# Arduino_PowerMeter_Shield.net
KiCad netlist of a schematic drawn in EAGLE
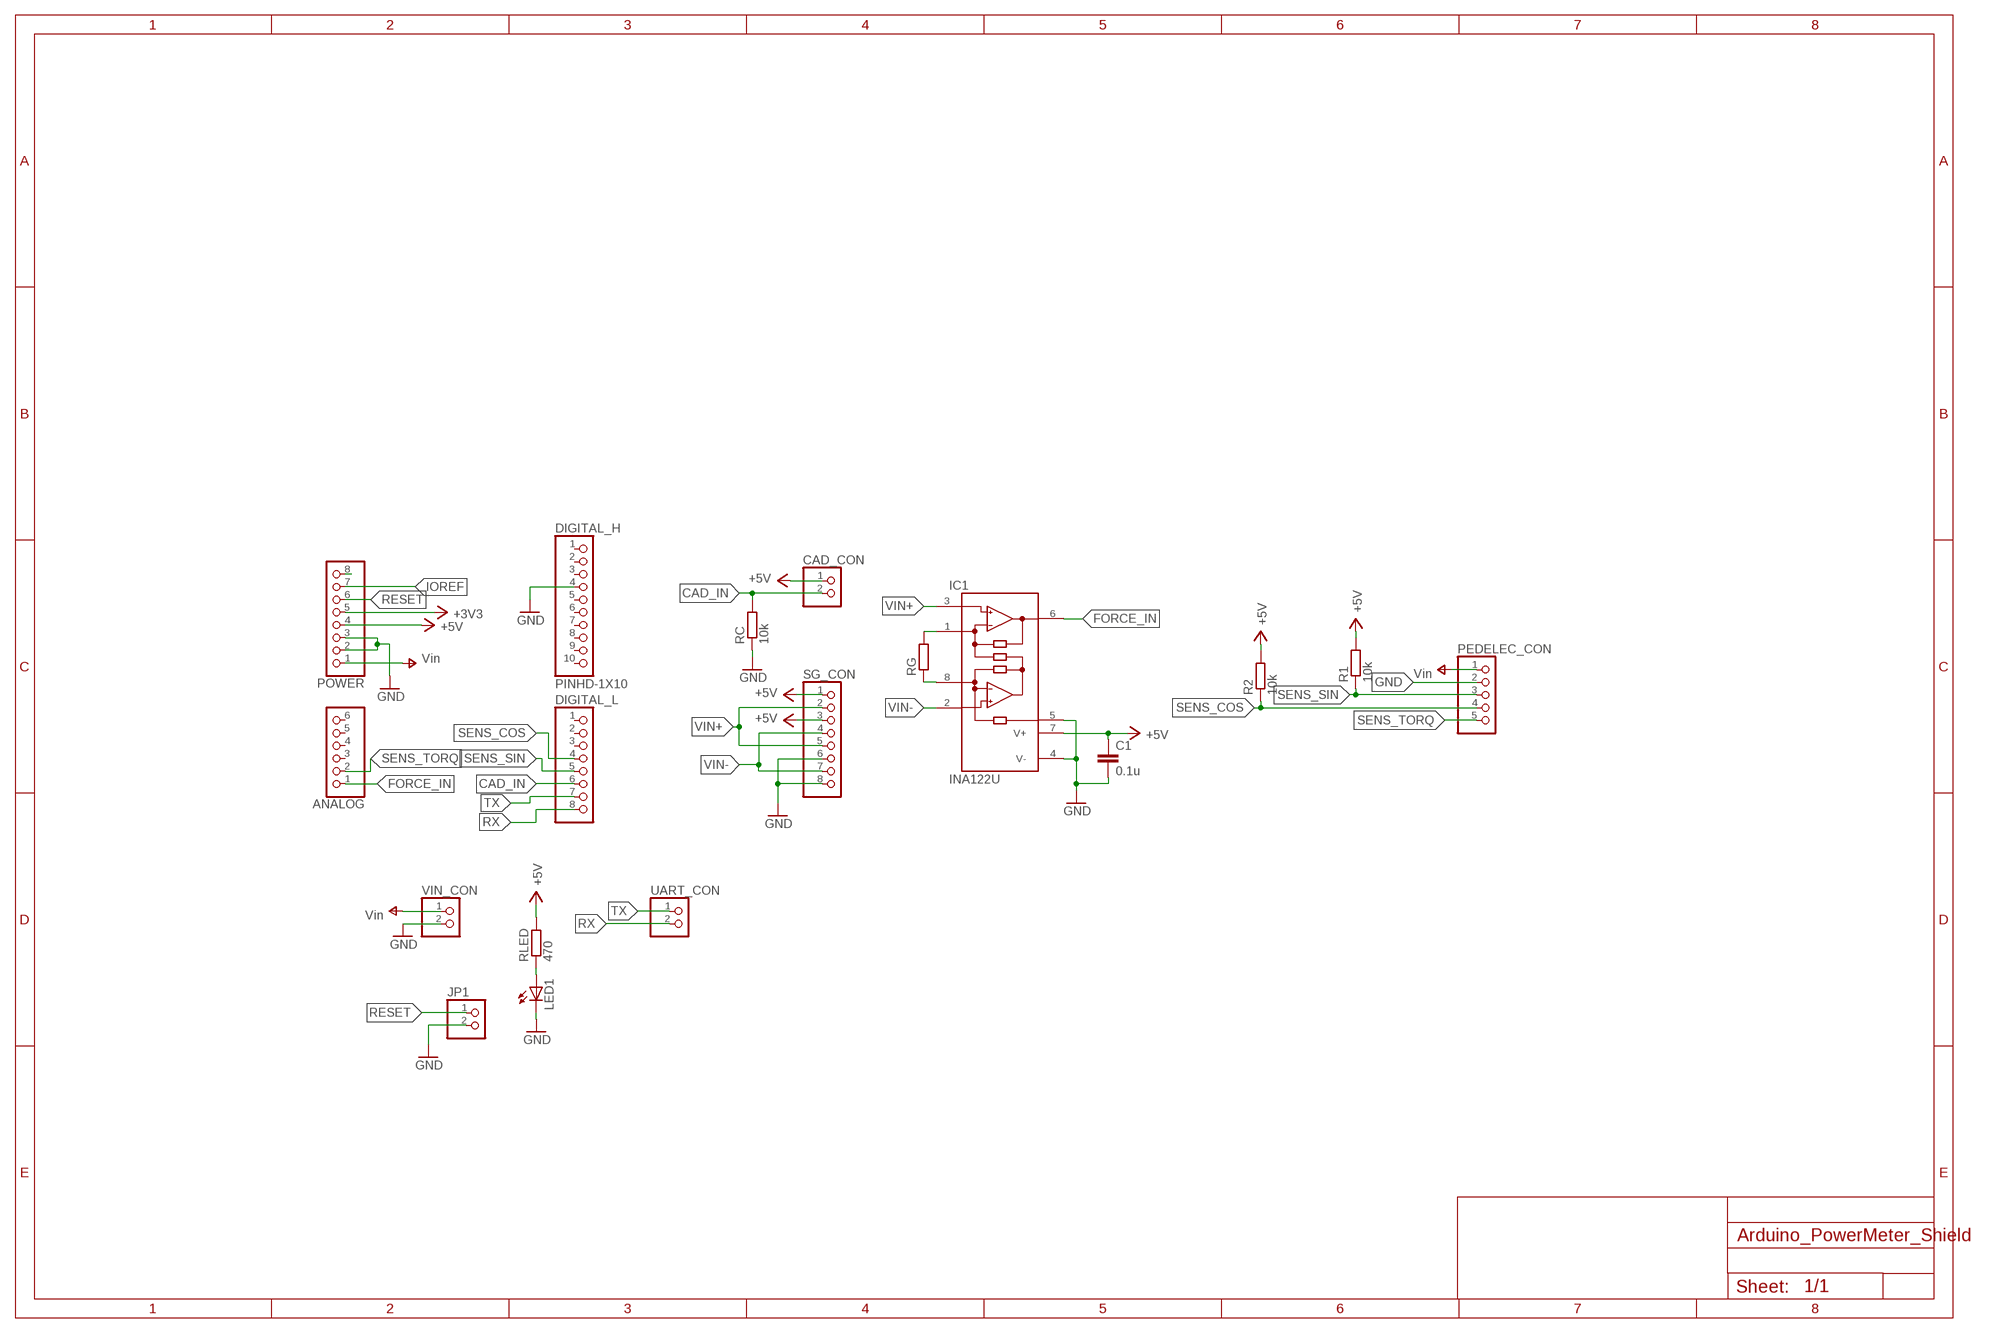
[diagram p0: schematic, sheet 1]

(export (version "E")
  (design (tool "Eeschema 10.0.6"))
  (components
    (comp (ref "ANALOG")
      (value "PINHD-1X6B")
      (footprint "eagle-import:1X06-BIG")
      (libsource (lib "eagle-import") (part "PINHD-1X6B"))
    )
    (comp (ref "C1")
      (value "0.1u")
      (footprint "eagle-import:C0603")
      (libsource (lib "eagle-import") (part "C-EUC0603"))
    )
    (comp (ref "CAD_CON")
      (value "PINHD-1X2/90")
      (footprint "eagle-import:1X02_90")
      (libsource (lib "eagle-import") (part "PINHD-1X2/90"))
    )
    (comp (ref "DIGITAL_H")
      (value "PINHD-1X10")
      (footprint "eagle-import:1X10-BIG")
      (libsource (lib "eagle-import") (part "PINHD-1X10"))
    )
    (comp (ref "DIGITAL_L")
      (value "PINHD-1X8BIG")
      (footprint "eagle-import:1X08-BIG")
      (libsource (lib "eagle-import") (part "PINHD-1X8BIG"))
    )
    (comp (ref "IC1")
      (value "INA122U")
      (footprint "eagle-import:SO08")
      (libsource (lib "eagle-import") (part "INA122U"))
    )
    (comp (ref "JP1")
      (value "PINHD-1X2")
      (footprint "eagle-import:1X02")
      (libsource (lib "eagle-import") (part "PINHD-1X2"))
    )
    (comp (ref "LED1")
      (value "LEDCHIPLED_0603")
      (footprint "eagle-import:CHIPLED_0603")
      (libsource (lib "eagle-import") (part "LEDCHIPLED_0603"))
    )
    (comp (ref "PEDELEC_CON")
      (value "PINHD-1X5/90")
      (footprint "eagle-import:1X05_90")
      (libsource (lib "eagle-import") (part "PINHD-1X5/90"))
    )
    (comp (ref "POWER")
      (value "PINHD-1X8BIG")
      (footprint "eagle-import:1X08-BIG")
      (libsource (lib "eagle-import") (part "PINHD-1X8BIG"))
    )
    (comp (ref "R1")
      (value "10k")
      (footprint "eagle-import:R0603")
      (libsource (lib "eagle-import") (part "R-EU_R0603"))
    )
    (comp (ref "R2")
      (value "10k")
      (footprint "eagle-import:R0603")
      (libsource (lib "eagle-import") (part "R-EU_R0603"))
    )
    (comp (ref "RC")
      (value "10k")
      (footprint "eagle-import:R0603")
      (libsource (lib "eagle-import") (part "R-EU_R0603"))
    )
    (comp (ref "RG")
      (value "R-EU_R0603")
      (footprint "eagle-import:R0603")
      (libsource (lib "eagle-import") (part "R-EU_R0603"))
    )
    (comp (ref "RLED")
      (value "470")
      (footprint "eagle-import:R0603")
      (libsource (lib "eagle-import") (part "R-EU_R0603"))
    )
    (comp (ref "SG_CON")
      (value "PINHD-1X8/90")
      (footprint "eagle-import:1X08_90")
      (libsource (lib "eagle-import") (part "PINHD-1X8/90"))
    )
    (comp (ref "UART_CON")
      (value "PINHD-1X2/90")
      (footprint "eagle-import:1X02_90")
      (libsource (lib "eagle-import") (part "PINHD-1X2/90"))
    )
    (comp (ref "VIN_CON")
      (value "PINHD-1X2/90")
      (footprint "eagle-import:1X02_90")
      (libsource (lib "eagle-import") (part "PINHD-1X2/90"))
    )
  )
  (nets
    (net (code "1") (name "+3V3") (class "Default")
      (node (ref "POWER") (pin "5") (pinfunction "5_5") (pintype "passive"))
    )
    (net (code "2") (name "+5V") (class "Default")
      (node (ref "C1") (pin "1") (pinfunction "1_1") (pintype "passive"))
      (node (ref "CAD_CON") (pin "1") (pinfunction "1_1") (pintype "passive"))
      (node (ref "IC1") (pin "7") (pinfunction "V+_7") (pintype "power_in"))
      (node (ref "POWER") (pin "4") (pinfunction "4_4") (pintype "passive"))
      (node (ref "R1") (pin "2") (pinfunction "2_2") (pintype "passive"))
      (node (ref "R2") (pin "2") (pinfunction "2_2") (pintype "passive"))
      (node (ref "RLED") (pin "2") (pinfunction "2_2") (pintype "passive"))
      (node (ref "SG_CON") (pin "1") (pinfunction "1_1") (pintype "passive"))
      (node (ref "SG_CON") (pin "3") (pinfunction "3_3") (pintype "passive"))
    )
    (net (code "3") (name "CAD_IN") (class "Default")
      (node (ref "CAD_CON") (pin "2") (pinfunction "2_2") (pintype "passive"))
      (node (ref "DIGITAL_L") (pin "6") (pinfunction "6_6") (pintype "passive"))
      (node (ref "RC") (pin "2") (pinfunction "2_2") (pintype "passive"))
    )
    (net (code "4") (name "FORCE_IN") (class "Default")
      (node (ref "ANALOG") (pin "1") (pinfunction "1_1") (pintype "passive"))
      (node (ref "IC1") (pin "6") (pinfunction "OUT_6") (pintype "output"))
    )
    (net (code "5") (name "GND") (class "Default")
      (node (ref "C1") (pin "2") (pinfunction "2_2") (pintype "passive"))
      (node (ref "DIGITAL_H") (pin "4") (pinfunction "4_4") (pintype "passive"))
      (node (ref "IC1") (pin "4") (pinfunction "V-_4") (pintype "power_in"))
      (node (ref "IC1") (pin "5") (pinfunction "REF_5") (pintype "passive"))
      (node (ref "JP1") (pin "2") (pinfunction "2_2") (pintype "passive"))
      (node (ref "LED1") (pin "C") (pinfunction "C_C") (pintype "passive"))
      (node (ref "PEDELEC_CON") (pin "2") (pinfunction "2_2") (pintype "passive"))
      (node (ref "POWER") (pin "2") (pinfunction "2_2") (pintype "passive"))
      (node (ref "POWER") (pin "3") (pinfunction "3_3") (pintype "passive"))
      (node (ref "RC") (pin "1") (pinfunction "1_1") (pintype "passive"))
      (node (ref "SG_CON") (pin "6") (pinfunction "6_6") (pintype "passive"))
      (node (ref "SG_CON") (pin "8") (pinfunction "8_8") (pintype "passive"))
      (node (ref "VIN_CON") (pin "2") (pinfunction "2_2") (pintype "passive"))
    )
    (net (code "6") (name "IOREF") (class "Default")
      (node (ref "POWER") (pin "7") (pinfunction "7_7") (pintype "passive"))
    )
    (net (code "7") (name "Net-(IC1-RG-Pad1)") (class "Default")
      (node (ref "IC1") (pin "1") (pinfunction "RG_1") (pintype "passive"))
      (node (ref "RG") (pin "2") (pinfunction "2_2") (pintype "passive"))
    )
    (net (code "8") (name "Net-(IC1-RG-Pad8)") (class "Default")
      (node (ref "IC1") (pin "8") (pinfunction "RG_8") (pintype "passive"))
      (node (ref "RG") (pin "1") (pinfunction "1_1") (pintype "passive"))
    )
    (net (code "9") (name "Net-(LED1-PadA)") (class "Default")
      (node (ref "LED1") (pin "A") (pinfunction "A_A") (pintype "passive"))
      (node (ref "RLED") (pin "1") (pinfunction "1_1") (pintype "passive"))
    )
    (net (code "10") (name "RESET") (class "Default")
      (node (ref "JP1") (pin "1") (pinfunction "1_1") (pintype "passive"))
      (node (ref "POWER") (pin "6") (pinfunction "6_6") (pintype "passive"))
    )
    (net (code "11") (name "RX") (class "Default")
      (node (ref "DIGITAL_L") (pin "8") (pinfunction "8_8") (pintype "passive"))
      (node (ref "UART_CON") (pin "2") (pinfunction "2_2") (pintype "passive"))
    )
    (net (code "12") (name "SENS_COS") (class "Default")
      (node (ref "DIGITAL_L") (pin "4") (pinfunction "4_4") (pintype "passive"))
      (node (ref "PEDELEC_CON") (pin "4") (pinfunction "4_4") (pintype "passive"))
      (node (ref "R2") (pin "1") (pinfunction "1_1") (pintype "passive"))
    )
    (net (code "13") (name "SENS_SIN") (class "Default")
      (node (ref "DIGITAL_L") (pin "5") (pinfunction "5_5") (pintype "passive"))
      (node (ref "PEDELEC_CON") (pin "3") (pinfunction "3_3") (pintype "passive"))
      (node (ref "R1") (pin "1") (pinfunction "1_1") (pintype "passive"))
    )
    (net (code "14") (name "SENS_TORQ") (class "Default")
      (node (ref "ANALOG") (pin "2") (pinfunction "2_2") (pintype "passive"))
      (node (ref "PEDELEC_CON") (pin "5") (pinfunction "5_5") (pintype "passive"))
    )
    (net (code "15") (name "TX") (class "Default")
      (node (ref "DIGITAL_L") (pin "7") (pinfunction "7_7") (pintype "passive"))
      (node (ref "UART_CON") (pin "1") (pinfunction "1_1") (pintype "passive"))
    )
    (net (code "16") (name "VIN+") (class "Default")
      (node (ref "IC1") (pin "3") (pinfunction "+IN_3") (pintype "input"))
      (node (ref "SG_CON") (pin "2") (pinfunction "2_2") (pintype "passive"))
      (node (ref "SG_CON") (pin "5") (pinfunction "5_5") (pintype "passive"))
    )
    (net (code "17") (name "VIN-") (class "Default")
      (node (ref "IC1") (pin "2") (pinfunction "-IN_2") (pintype "input"))
      (node (ref "SG_CON") (pin "4") (pinfunction "4_4") (pintype "passive"))
      (node (ref "SG_CON") (pin "7") (pinfunction "7_7") (pintype "passive"))
    )
    (net (code "18") (name "Vin") (class "Default")
      (node (ref "PEDELEC_CON") (pin "1") (pinfunction "1_1") (pintype "passive"))
      (node (ref "POWER") (pin "1") (pinfunction "1_1") (pintype "passive"))
      (node (ref "VIN_CON") (pin "1") (pinfunction "1_1") (pintype "passive"))
    )
    (net (code "19") (name "unconnected-(ANALOG-Pad3)") (class "Default")
      (node (ref "ANALOG") (pin "3") (pinfunction "3_3") (pintype "passive"))
    )
    (net (code "20") (name "unconnected-(ANALOG-Pad4)") (class "Default")
      (node (ref "ANALOG") (pin "4") (pinfunction "4_4") (pintype "passive"))
    )
    (net (code "21") (name "unconnected-(ANALOG-Pad5)") (class "Default")
      (node (ref "ANALOG") (pin "5") (pinfunction "5_5") (pintype "passive"))
    )
    (net (code "22") (name "unconnected-(ANALOG-Pad6)") (class "Default")
      (node (ref "ANALOG") (pin "6") (pinfunction "6_6") (pintype "passive"))
    )
    (net (code "23") (name "unconnected-(DIGITAL_H-Pad1)") (class "Default")
      (node (ref "DIGITAL_H") (pin "1") (pinfunction "1_1") (pintype "passive"))
    )
    (net (code "24") (name "unconnected-(DIGITAL_H-Pad2)") (class "Default")
      (node (ref "DIGITAL_H") (pin "2") (pinfunction "2_2") (pintype "passive"))
    )
    (net (code "25") (name "unconnected-(DIGITAL_H-Pad3)") (class "Default")
      (node (ref "DIGITAL_H") (pin "3") (pinfunction "3_3") (pintype "passive"))
    )
    (net (code "26") (name "unconnected-(DIGITAL_H-Pad5)") (class "Default")
      (node (ref "DIGITAL_H") (pin "5") (pinfunction "5_5") (pintype "passive"))
    )
    (net (code "27") (name "unconnected-(DIGITAL_H-Pad6)") (class "Default")
      (node (ref "DIGITAL_H") (pin "6") (pinfunction "6_6") (pintype "passive"))
    )
    (net (code "28") (name "unconnected-(DIGITAL_H-Pad7)") (class "Default")
      (node (ref "DIGITAL_H") (pin "7") (pinfunction "7_7") (pintype "passive"))
    )
    (net (code "29") (name "unconnected-(DIGITAL_H-Pad8)") (class "Default")
      (node (ref "DIGITAL_H") (pin "8") (pinfunction "8_8") (pintype "passive"))
    )
    (net (code "30") (name "unconnected-(DIGITAL_H-Pad9)") (class "Default")
      (node (ref "DIGITAL_H") (pin "9") (pinfunction "9_9") (pintype "passive"))
    )
    (net (code "31") (name "unconnected-(DIGITAL_H-Pad10)") (class "Default")
      (node (ref "DIGITAL_H") (pin "10") (pinfunction "10_10") (pintype "passive"))
    )
    (net (code "32") (name "unconnected-(DIGITAL_L-Pad1)") (class "Default")
      (node (ref "DIGITAL_L") (pin "1") (pinfunction "1_1") (pintype "passive"))
    )
    (net (code "33") (name "unconnected-(DIGITAL_L-Pad2)") (class "Default")
      (node (ref "DIGITAL_L") (pin "2") (pinfunction "2_2") (pintype "passive"))
    )
    (net (code "34") (name "unconnected-(DIGITAL_L-Pad3)") (class "Default")
      (node (ref "DIGITAL_L") (pin "3") (pinfunction "3_3") (pintype "passive"))
    )
    (net (code "35") (name "unconnected-(POWER-Pad8)") (class "Default")
      (node (ref "POWER") (pin "8") (pinfunction "8_8") (pintype "passive"))
    )
  )
)
